# SNES_DRONE_MCU.net
KiCad netlist of a schematic drawn in Altium Designer
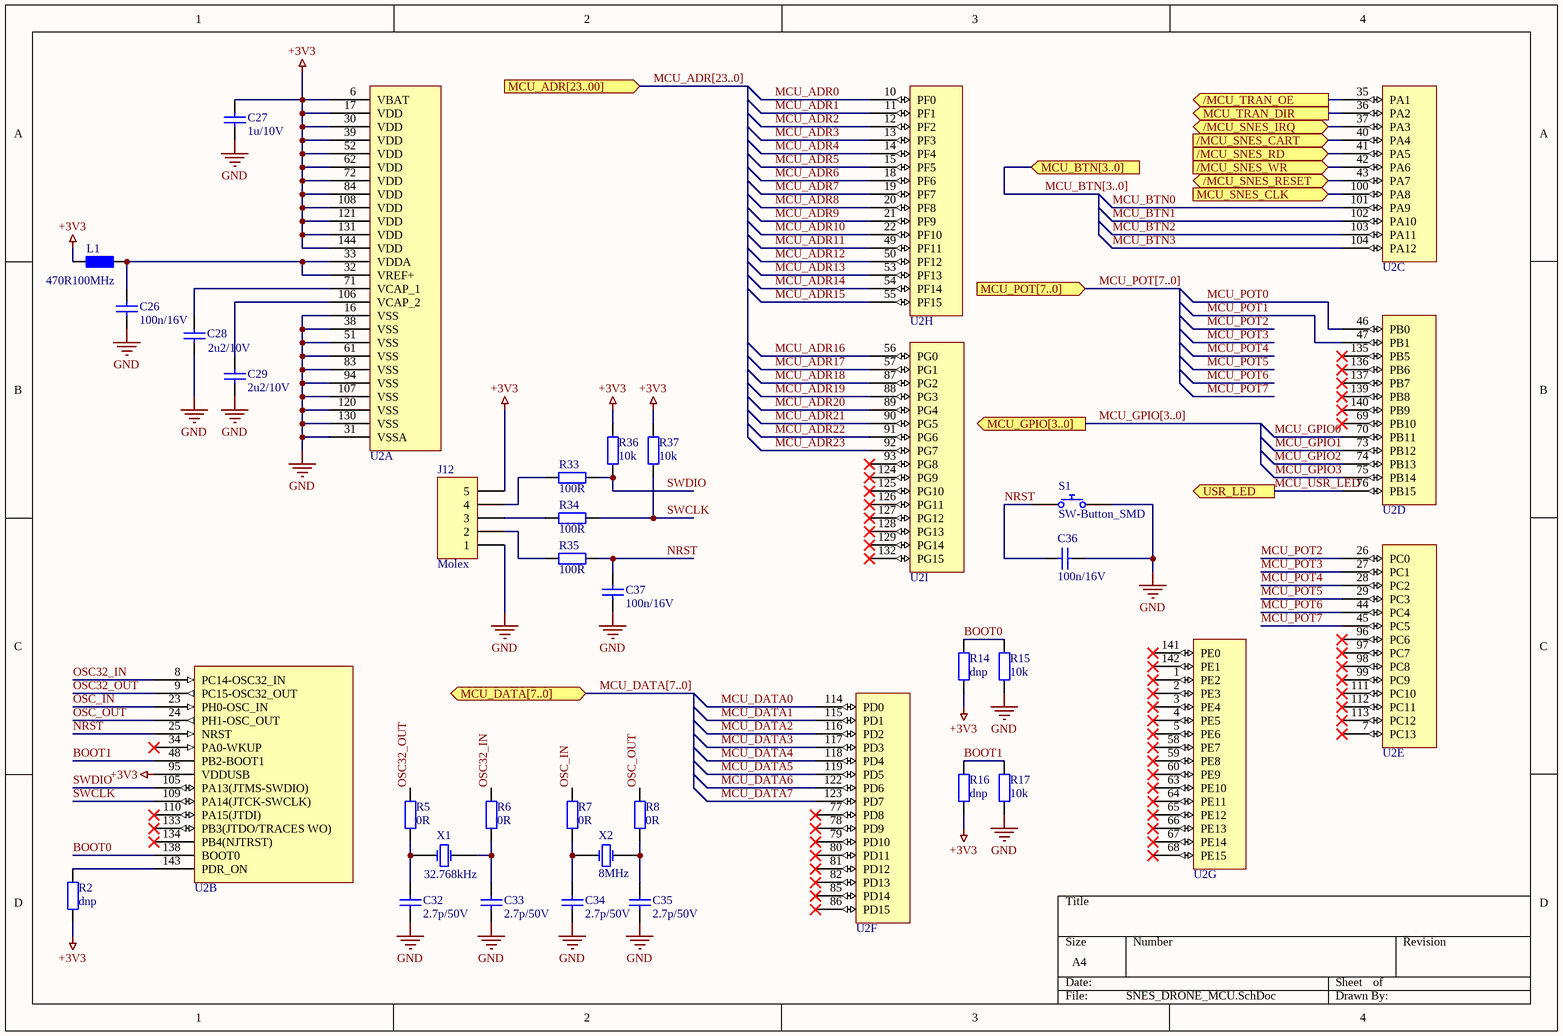
[diagram p0: SNES_DRONE_MCU.SchDoc]

(export (version "E")
  (design (tool "Eeschema 10.0.6"))
  (components
    (comp (ref "C26")
      (value "100n/16V")
      (footprint "0402_RES")
      (description "Keramikvielschichtkondensator, SMD, 0.1 µF, 16 V, 0402 [Metrisch 1005], ± 10%, X5R, Baureihe MC")
      (libsource (lib "My_Integrated_Library") (part "Cap_100n_0402"))
    )
    (comp (ref "C27")
      (value "1u/10V")
      (footprint "0603_RES")
      (description "Keramikvielschichtkondensator, SMD, 1 µF, 10 V, 0603 [Metrisch 1608], ± 20%, X5R, WCAP-CSGP Series")
      (libsource (lib "My_Integrated_Library") (part "Cap_1u_0603"))
    )
    (comp (ref "C28")
      (value "2u2/10V")
      (footprint "0603_RES")
      (libsource (lib "My_Integrated_Library") (part "Cap_2u2_0603"))
    )
    (comp (ref "C29")
      (value "2u2/10V")
      (footprint "0603_RES")
      (libsource (lib "My_Integrated_Library") (part "Cap_2u2_0603"))
    )
    (comp (ref "C32")
      (value "2.7p/50V")
      (footprint "0402_RES")
      (description "Keramikvielschichtkondensator, SMD, 2.7 pF, 50 V, 0402 [Metrisch 1005], ± 0.25pF, C0G / NP0")
      (libsource (lib "My_Integrated_Library") (part "Cap_2p7_0402"))
    )
    (comp (ref "C33")
      (value "2.7p/50V")
      (footprint "0402_RES")
      (description "Keramikvielschichtkondensator, SMD, 2.7 pF, 50 V, 0402 [Metrisch 1005], ± 0.25pF, C0G / NP0")
      (libsource (lib "My_Integrated_Library") (part "Cap_2p7_0402"))
    )
    (comp (ref "C34")
      (value "2.7p/50V")
      (footprint "0402_RES")
      (description "Keramikvielschichtkondensator, SMD, 2.7 pF, 50 V, 0402 [Metrisch 1005], ± 0.25pF, C0G / NP0")
      (libsource (lib "My_Integrated_Library") (part "Cap_2p7_0402"))
    )
    (comp (ref "C35")
      (value "2.7p/50V")
      (footprint "0402_RES")
      (description "Keramikvielschichtkondensator, SMD, 2.7 pF, 50 V, 0402 [Metrisch 1005], ± 0.25pF, C0G / NP0")
      (libsource (lib "My_Integrated_Library") (part "Cap_2p7_0402"))
    )
    (comp (ref "C36")
      (value "100n/16V")
      (footprint "0402_RES")
      (description "Keramikvielschichtkondensator, SMD, 0.1 µF, 16 V, 0402 [Metrisch 1005], ± 10%, X5R, Baureihe MC")
      (libsource (lib "My_Integrated_Library") (part "Cap_100n_0402"))
    )
    (comp (ref "C37")
      (value "100n/16V")
      (footprint "0402_RES")
      (description "Keramikvielschichtkondensator, SMD, 0.1 µF, 16 V, 0402 [Metrisch 1005], ± 10%, X5R, Baureihe MC")
      (libsource (lib "My_Integrated_Library") (part "Cap_100n_0402"))
    )
    (comp (ref "J12")
      (value "MOLEX_22-27-2051")
      (footprint "MOLEX_22-27-2051")
      (description "5 pin molex connector")
      (fields (field (name "MANUFACTURER 1") "Molex"))
      (libsource (lib "My_Integrated_Library") (part "MOLEX_22-27-2051"))
    )
    (comp (ref "L1")
      (value "470R100MHz")
      (footprint "0603_RES")
      (description "BLM18PG471SN1D -  Ferritperle, 0603 [Metrisch 1608], 470 ohm, 1 A, Baureihe BLM18P, 0.2 ohm, ± 25%")
      (libsource (lib "My_Integrated_Library") (part "FER_0603_470R"))
    )
    (comp (ref "R2")
      (value "dnp")
      (footprint "0603_DNP")
      (fields (field (name "Comment") "DNP"))
      (libsource (lib "My_Integrated_Library") (part "RES_DNP"))
    )
    (comp (ref "R5")
      (value "0R")
      (footprint "0603_RES")
      (description "YAGEO 0R")
      (libsource (lib "My_Integrated_Library") (part "RES_0603_0R"))
    )
    (comp (ref "R6")
      (value "0R")
      (footprint "0603_RES")
      (description "YAGEO 0R")
      (libsource (lib "My_Integrated_Library") (part "RES_0603_0R"))
    )
    (comp (ref "R7")
      (value "0R")
      (footprint "0603_RES")
      (description "YAGEO 0R")
      (libsource (lib "My_Integrated_Library") (part "RES_0603_0R"))
    )
    (comp (ref "R8")
      (value "0R")
      (footprint "0603_RES")
      (description "YAGEO 0R")
      (libsource (lib "My_Integrated_Library") (part "RES_0603_0R"))
    )
    (comp (ref "R14")
      (value "dnp")
      (footprint "0603_DNP")
      (fields (field (name "Comment") "DNP"))
      (libsource (lib "My_Integrated_Library") (part "RES_DNP"))
    )
    (comp (ref "R15")
      (value "10k")
      (footprint "0603_RES")
      (description "YAGEO 10kOhm 100mW ± 1%")
      (fields (field (name "Comment") "10kOhm 100mW"))
      (libsource (lib "My_Integrated_Library") (part "RES_0603_10k_100mW"))
    )
    (comp (ref "R16")
      (value "dnp")
      (footprint "0603_DNP")
      (fields (field (name "Comment") "DNP"))
      (libsource (lib "My_Integrated_Library") (part "RES_DNP"))
    )
    (comp (ref "R17")
      (value "10k")
      (footprint "0603_RES")
      (description "YAGEO 10kOhm 100mW ± 1%")
      (fields (field (name "Comment") "10kOhm 100mW"))
      (libsource (lib "My_Integrated_Library") (part "RES_0603_10k_100mW"))
    )
    (comp (ref "R33")
      (value "100R")
      (footprint "0603_RES")
      (description "PANASONIC ELECTRONIC COMPONENTS 100Ohm 100mW ± 1%")
      (fields (field (name "Comment") "100Ohm 100mW"))
      (libsource (lib "My_Integrated_Library") (part "RES_0603_100_100mW"))
    )
    (comp (ref "R34")
      (value "100R")
      (footprint "0603_RES")
      (description "PANASONIC ELECTRONIC COMPONENTS 100Ohm 100mW ± 1%")
      (fields (field (name "Comment") "100Ohm 100mW"))
      (libsource (lib "My_Integrated_Library") (part "RES_0603_100_100mW"))
    )
    (comp (ref "R35")
      (value "100R")
      (footprint "0603_RES")
      (description "PANASONIC ELECTRONIC COMPONENTS 100Ohm 100mW ± 1%")
      (fields (field (name "Comment") "100Ohm 100mW"))
      (libsource (lib "My_Integrated_Library") (part "RES_0603_100_100mW"))
    )
    (comp (ref "R36")
      (value "10k")
      (footprint "0603_RES")
      (description "YAGEO 10kOhm 100mW ± 1%")
      (fields (field (name "Comment") "10kOhm 100mW"))
      (libsource (lib "My_Integrated_Library") (part "RES_0603_10k_100mW"))
    )
    (comp (ref "R37")
      (value "10k")
      (footprint "0603_RES")
      (description "YAGEO 10kOhm 100mW ± 1%")
      (fields (field (name "Comment") "10kOhm 100mW"))
      (libsource (lib "My_Integrated_Library") (part "RES_0603_10k_100mW"))
    )
    (comp (ref "S1")
      (value "SW-Button_SMD")
      (footprint "SKQGAFE010")
      (description "ALPS SMD Push Button")
      (libsource (lib "My_Integrated_Library") (part "SW-Button_SMD"))
    )
    (comp (ref "U2")
      (value "STM32F446ZE")
      (footprint "LQFP144_SMALL_PADS")
      (description "ARM Cortex-M4, 180MHz, 512KB, 128KB")
      (libsource (lib "My_Schlib") (part "STM32F446ZE"))
    )
    (comp (ref "X1")
      (value "32.768kHz")
      (footprint "XTAL_32768khz")
      (libsource (lib "My_Integrated_Library") (part "XTAL_32.768kHz"))
    )
    (comp (ref "X2")
      (value "8MHz")
      (footprint "XTAL_8MHZ")
      (libsource (lib "My_Integrated_Library") (part "XTAL_8MHz"))
    )
  )
  (nets
    (net (code "1") (name "+3V3") (class "Default")
      (node (ref "C27") (pin "2") (pinfunction "2_2") (pintype "passive"))
      (node (ref "J12") (pin "5") (pinfunction "5_5") (pintype "passive"))
      (node (ref "L1") (pin "1") (pinfunction "1_1") (pintype "passive"))
      (node (ref "R14") (pin "1") (pinfunction "1_1") (pintype "passive"))
      (node (ref "R16") (pin "1") (pinfunction "1_1") (pintype "passive"))
      (node (ref "R2") (pin "1") (pinfunction "1_1") (pintype "passive"))
      (node (ref "R36") (pin "2") (pinfunction "2_2") (pintype "passive"))
      (node (ref "R37") (pin "2") (pinfunction "2_2") (pintype "passive"))
      (node (ref "U2") (pin "108") (pinfunction "VDD_108") (pintype "power_in"))
      (node (ref "U2") (pin "121") (pinfunction "VDD_121") (pintype "power_in"))
      (node (ref "U2") (pin "131") (pinfunction "VDD_131") (pintype "power_in"))
      (node (ref "U2") (pin "144") (pinfunction "VDD_144") (pintype "power_in"))
      (node (ref "U2") (pin "17") (pinfunction "VDD_17") (pintype "power_in"))
      (node (ref "U2") (pin "30") (pinfunction "VDD_30") (pintype "power_in"))
      (node (ref "U2") (pin "39") (pinfunction "VDD_39") (pintype "power_in"))
      (node (ref "U2") (pin "52") (pinfunction "VDD_52") (pintype "power_in"))
      (node (ref "U2") (pin "6") (pinfunction "VBAT_6") (pintype "power_in"))
      (node (ref "U2") (pin "62") (pinfunction "VDD_62") (pintype "power_in"))
      (node (ref "U2") (pin "72") (pinfunction "VDD_72") (pintype "power_in"))
      (node (ref "U2") (pin "84") (pinfunction "VDD_84") (pintype "power_in"))
      (node (ref "U2") (pin "95") (pinfunction "VDDUSB_95") (pintype "power_in"))
    )
    (net (code "2") (name "/BOOT0") (class "Default")
      (node (ref "R14") (pin "2") (pinfunction "2_2") (pintype "passive"))
      (node (ref "R15") (pin "2") (pinfunction "2_2") (pintype "passive"))
      (node (ref "U2") (pin "138") (pinfunction "BOOT0_138") (pintype "passive"))
    )
    (net (code "3") (name "/BOOT1") (class "Default")
      (node (ref "R16") (pin "2") (pinfunction "2_2") (pintype "passive"))
      (node (ref "R17") (pin "2") (pinfunction "2_2") (pintype "passive"))
      (node (ref "U2") (pin "48") (pinfunction "PB2-BOOT1_48") (pintype "passive"))
    )
    (net (code "4") (name "/MCU_ADR0") (class "Default")
      (node (ref "U2") (pin "10") (pinfunction "PF0_10") (pintype "bidirectional"))
    )
    (net (code "5") (name "/MCU_ADR1") (class "Default")
      (node (ref "U2") (pin "11") (pinfunction "PF1_11") (pintype "bidirectional"))
    )
    (net (code "6") (name "/MCU_ADR2") (class "Default")
      (node (ref "U2") (pin "12") (pinfunction "PF2_12") (pintype "bidirectional"))
    )
    (net (code "7") (name "/MCU_ADR3") (class "Default")
      (node (ref "U2") (pin "13") (pinfunction "PF3_13") (pintype "bidirectional"))
    )
    (net (code "8") (name "/MCU_ADR4") (class "Default")
      (node (ref "U2") (pin "14") (pinfunction "PF4_14") (pintype "bidirectional"))
    )
    (net (code "9") (name "/MCU_ADR5") (class "Default")
      (node (ref "U2") (pin "15") (pinfunction "PF5_15") (pintype "bidirectional"))
    )
    (net (code "10") (name "/MCU_ADR6") (class "Default")
      (node (ref "U2") (pin "18") (pinfunction "PF6_18") (pintype "bidirectional"))
    )
    (net (code "11") (name "/MCU_ADR7") (class "Default")
      (node (ref "U2") (pin "19") (pinfunction "PF7_19") (pintype "bidirectional"))
    )
    (net (code "12") (name "/MCU_ADR8") (class "Default")
      (node (ref "U2") (pin "20") (pinfunction "PF8_20") (pintype "bidirectional"))
    )
    (net (code "13") (name "/MCU_ADR9") (class "Default")
      (node (ref "U2") (pin "21") (pinfunction "PF9_21") (pintype "bidirectional"))
    )
    (net (code "14") (name "/MCU_ADR10") (class "Default")
      (node (ref "U2") (pin "22") (pinfunction "PF10_22") (pintype "bidirectional"))
    )
    (net (code "15") (name "/MCU_ADR11") (class "Default")
      (node (ref "U2") (pin "49") (pinfunction "PF11_49") (pintype "bidirectional"))
    )
    (net (code "16") (name "/MCU_ADR12") (class "Default")
      (node (ref "U2") (pin "50") (pinfunction "PF12_50") (pintype "bidirectional"))
    )
    (net (code "17") (name "/MCU_ADR13") (class "Default")
      (node (ref "U2") (pin "53") (pinfunction "PF13_53") (pintype "bidirectional"))
    )
    (net (code "18") (name "/MCU_ADR14") (class "Default")
      (node (ref "U2") (pin "54") (pinfunction "PF14_54") (pintype "bidirectional"))
    )
    (net (code "19") (name "/MCU_ADR15") (class "Default")
      (node (ref "U2") (pin "55") (pinfunction "PF15_55") (pintype "bidirectional"))
    )
    (net (code "20") (name "/MCU_ADR16") (class "Default")
      (node (ref "U2") (pin "56") (pinfunction "PG0_56") (pintype "bidirectional"))
    )
    (net (code "21") (name "/MCU_ADR17") (class "Default")
      (node (ref "U2") (pin "57") (pinfunction "PG1_57") (pintype "bidirectional"))
    )
    (net (code "22") (name "/MCU_ADR18") (class "Default")
      (node (ref "U2") (pin "87") (pinfunction "PG2_87") (pintype "bidirectional"))
    )
    (net (code "23") (name "/MCU_ADR19") (class "Default")
      (node (ref "U2") (pin "88") (pinfunction "PG3_88") (pintype "bidirectional"))
    )
    (net (code "24") (name "/MCU_ADR20") (class "Default")
      (node (ref "U2") (pin "89") (pinfunction "PG4_89") (pintype "bidirectional"))
    )
    (net (code "25") (name "/MCU_ADR21") (class "Default")
      (node (ref "U2") (pin "90") (pinfunction "PG5_90") (pintype "bidirectional"))
    )
    (net (code "26") (name "/MCU_ADR22") (class "Default")
      (node (ref "U2") (pin "91") (pinfunction "PG6_91") (pintype "bidirectional"))
    )
    (net (code "27") (name "/MCU_ADR23") (class "Default")
      (node (ref "U2") (pin "92") (pinfunction "PG7_92") (pintype "bidirectional"))
    )
    (net (code "29") (name "/MCU_BTN0") (class "Default")
      (node (ref "U2") (pin "101") (pinfunction "PA9_101") (pintype "bidirectional"))
    )
    (net (code "30") (name "/MCU_BTN1") (class "Default")
      (node (ref "U2") (pin "102") (pinfunction "PA10_102") (pintype "bidirectional"))
    )
    (net (code "31") (name "/MCU_BTN2") (class "Default")
      (node (ref "U2") (pin "103") (pinfunction "PA11_103") (pintype "bidirectional"))
    )
    (net (code "32") (name "/MCU_BTN3") (class "Default")
      (node (ref "U2") (pin "104") (pinfunction "PA12_104") (pintype "bidirectional"))
    )
    (net (code "34") (name "/MCU_DATA0") (class "Default")
      (node (ref "U2") (pin "114") (pinfunction "PD0_114") (pintype "bidirectional"))
    )
    (net (code "35") (name "/MCU_DATA1") (class "Default")
      (node (ref "U2") (pin "115") (pinfunction "PD1_115") (pintype "bidirectional"))
    )
    (net (code "36") (name "/MCU_DATA2") (class "Default")
      (node (ref "U2") (pin "116") (pinfunction "PD2_116") (pintype "bidirectional"))
    )
    (net (code "37") (name "/MCU_DATA3") (class "Default")
      (node (ref "U2") (pin "117") (pinfunction "PD3_117") (pintype "bidirectional"))
    )
    (net (code "38") (name "/MCU_DATA4") (class "Default")
      (node (ref "U2") (pin "118") (pinfunction "PD4_118") (pintype "bidirectional"))
    )
    (net (code "39") (name "/MCU_DATA5") (class "Default")
      (node (ref "U2") (pin "119") (pinfunction "PD5_119") (pintype "bidirectional"))
    )
    (net (code "40") (name "/MCU_DATA6") (class "Default")
      (node (ref "U2") (pin "122") (pinfunction "PD6_122") (pintype "bidirectional"))
    )
    (net (code "41") (name "/MCU_DATA7") (class "Default")
      (node (ref "U2") (pin "123") (pinfunction "PD7_123") (pintype "bidirectional"))
    )
    (net (code "43") (name "/MCU_GPIO0") (class "Default")
      (node (ref "U2") (pin "70") (pinfunction "PB11_70") (pintype "bidirectional"))
    )
    (net (code "44") (name "/MCU_GPIO1") (class "Default")
      (node (ref "U2") (pin "73") (pinfunction "PB12_73") (pintype "bidirectional"))
    )
    (net (code "45") (name "/MCU_GPIO2") (class "Default")
      (node (ref "U2") (pin "74") (pinfunction "PB13_74") (pintype "bidirectional"))
    )
    (net (code "46") (name "/MCU_GPIO3") (class "Default")
      (node (ref "U2") (pin "75") (pinfunction "PB14_75") (pintype "bidirectional"))
    )
    (net (code "48") (name "/MCU_POT0") (class "Default")
      (node (ref "U2") (pin "46") (pinfunction "PB0_46") (pintype "bidirectional"))
    )
    (net (code "49") (name "/MCU_POT1") (class "Default")
      (node (ref "U2") (pin "47") (pinfunction "PB1_47") (pintype "bidirectional"))
    )
    (net (code "50") (name "/MCU_POT2") (class "Default")
      (node (ref "U2") (pin "26") (pinfunction "PC0_26") (pintype "bidirectional"))
    )
    (net (code "51") (name "/MCU_POT3") (class "Default")
      (node (ref "U2") (pin "27") (pinfunction "PC1_27") (pintype "bidirectional"))
    )
    (net (code "52") (name "/MCU_POT4") (class "Default")
      (node (ref "U2") (pin "28") (pinfunction "PC2_28") (pintype "bidirectional"))
    )
    (net (code "53") (name "/MCU_POT5") (class "Default")
      (node (ref "U2") (pin "29") (pinfunction "PC3_29") (pintype "bidirectional"))
    )
    (net (code "54") (name "/MCU_POT6") (class "Default")
      (node (ref "U2") (pin "44") (pinfunction "PC4_44") (pintype "bidirectional"))
    )
    (net (code "55") (name "/MCU_POT7") (class "Default")
      (node (ref "U2") (pin "45") (pinfunction "PC5_45") (pintype "bidirectional"))
    )
    (net (code "57") (name "/MCU_SNES_CLK") (class "Default")
      (node (ref "U2") (pin "100") (pinfunction "PA8_100") (pintype "bidirectional"))
    )
    (net (code "58") (name "/MCU_TRAN_DIR") (class "Default")
      (node (ref "U2") (pin "36") (pinfunction "PA2_36") (pintype "bidirectional"))
    )
    (net (code "59") (name "/MCU_USR_LED") (class "Default")
      (node (ref "U2") (pin "76") (pinfunction "PB15_76") (pintype "bidirectional"))
    )
    (net (code "60") (name "/NRST") (class "Default")
      (node (ref "C36") (pin "1") (pinfunction "1_1") (pintype "passive"))
      (node (ref "C37") (pin "2") (pinfunction "2_2") (pintype "passive"))
      (node (ref "R35") (pin "2") (pinfunction "2_2") (pintype "passive"))
      (node (ref "S1") (pin "1") (pinfunction "1_1") (pintype "passive"))
      (node (ref "U2") (pin "25") (pinfunction "NRST_25") (pintype "input"))
    )
    (net (code "61") (name "/OSC32_IN") (class "Default")
      (node (ref "R6") (pin "2") (pinfunction "2_2") (pintype "passive"))
      (node (ref "U2") (pin "8") (pinfunction "PC14-OSC32_IN_8") (pintype "input"))
    )
    (net (code "62") (name "/OSC32_OUT") (class "Default")
      (node (ref "R5") (pin "2") (pinfunction "2_2") (pintype "passive"))
      (node (ref "U2") (pin "9") (pinfunction "PC15-OSC32_OUT_9") (pintype "output"))
    )
    (net (code "63") (name "/OSC_IN") (class "Default")
      (node (ref "R7") (pin "2") (pinfunction "2_2") (pintype "passive"))
      (node (ref "U2") (pin "23") (pinfunction "PH0-OSC_IN_23") (pintype "input"))
    )
    (net (code "64") (name "/OSC_OUT") (class "Default")
      (node (ref "R8") (pin "2") (pinfunction "2_2") (pintype "passive"))
      (node (ref "U2") (pin "24") (pinfunction "PH1-OSC_OUT_24") (pintype "output"))
    )
    (net (code "65") (name "/SWCLK") (class "Default")
      (node (ref "R34") (pin "2") (pinfunction "2_2") (pintype "passive"))
      (node (ref "R37") (pin "1") (pinfunction "1_1") (pintype "passive"))
      (node (ref "U2") (pin "109") (pinfunction "PA14(JTCK-SWCLK)_109") (pintype "bidirectional"))
    )
    (net (code "66") (name "/SWDIO") (class "Default")
      (node (ref "R33") (pin "2") (pinfunction "2_2") (pintype "passive"))
      (node (ref "R36") (pin "1") (pinfunction "1_1") (pintype "passive"))
      (node (ref "U2") (pin "105") (pinfunction "PA13(JTMS-SWDIO)_105") (pintype "bidirectional"))
    )
    (net (code "67") (name "/{slash}MCU_SNES_CART") (class "Default")
      (node (ref "U2") (pin "40") (pinfunction "PA4_40") (pintype "bidirectional"))
    )
    (net (code "68") (name "/{slash}MCU_SNES_IRQ") (class "Default")
      (node (ref "U2") (pin "37") (pinfunction "PA3_37") (pintype "bidirectional"))
    )
    (net (code "69") (name "/{slash}MCU_SNES_RD") (class "Default")
      (node (ref "U2") (pin "41") (pinfunction "PA5_41") (pintype "bidirectional"))
    )
    (net (code "70") (name "/{slash}MCU_SNES_RESET") (class "Default")
      (node (ref "U2") (pin "43") (pinfunction "PA7_43") (pintype "bidirectional"))
    )
    (net (code "71") (name "/{slash}MCU_SNES_WR") (class "Default")
      (node (ref "U2") (pin "42") (pinfunction "PA6_42") (pintype "bidirectional"))
    )
    (net (code "72") (name "/{slash}MCU_TRAN_OE") (class "Default")
      (node (ref "U2") (pin "35") (pinfunction "PA1_35") (pintype "bidirectional"))
    )
    (net (code "73") (name "GND") (class "Default")
      (node (ref "C26") (pin "1") (pinfunction "1_1") (pintype "passive"))
      (node (ref "C27") (pin "1") (pinfunction "1_1") (pintype "passive"))
      (node (ref "C28") (pin "1") (pinfunction "1_1") (pintype "passive"))
      (node (ref "C29") (pin "1") (pinfunction "1_1") (pintype "passive"))
      (node (ref "C32") (pin "1") (pinfunction "1_1") (pintype "passive"))
      (node (ref "C33") (pin "1") (pinfunction "1_1") (pintype "passive"))
      (node (ref "C34") (pin "1") (pinfunction "1_1") (pintype "passive"))
      (node (ref "C35") (pin "1") (pinfunction "1_1") (pintype "passive"))
      (node (ref "C36") (pin "2") (pinfunction "2_2") (pintype "passive"))
      (node (ref "C37") (pin "1") (pinfunction "1_1") (pintype "passive"))
      (node (ref "J12") (pin "1") (pinfunction "1_1") (pintype "passive"))
      (node (ref "R15") (pin "1") (pinfunction "1_1") (pintype "passive"))
      (node (ref "R17") (pin "1") (pinfunction "1_1") (pintype "passive"))
      (node (ref "S1") (pin "3") (pinfunction "3_3") (pintype "passive"))
      (node (ref "U2") (pin "107") (pinfunction "VSS_107") (pintype "power_in"))
      (node (ref "U2") (pin "120") (pinfunction "VSS_120") (pintype "power_in"))
      (node (ref "U2") (pin "130") (pinfunction "VSS_130") (pintype "power_in"))
      (node (ref "U2") (pin "16") (pinfunction "VSS_16") (pintype "power_in"))
      (node (ref "U2") (pin "31") (pinfunction "VSSA_31") (pintype "power_in"))
      (node (ref "U2") (pin "38") (pinfunction "VSS_38") (pintype "power_in"))
      (node (ref "U2") (pin "51") (pinfunction "VSS_51") (pintype "power_in"))
      (node (ref "U2") (pin "61") (pinfunction "VSS_61") (pintype "power_in"))
      (node (ref "U2") (pin "83") (pinfunction "VSS_83") (pintype "power_in"))
      (node (ref "U2") (pin "94") (pinfunction "VSS_94") (pintype "power_in"))
    )
    (net (code "74") (name "Net-(C32-Pad2)") (class "Default")
      (node (ref "C32") (pin "2") (pinfunction "2_2") (pintype "passive"))
      (node (ref "R5") (pin "1") (pinfunction "1_1") (pintype "passive"))
      (node (ref "X1") (pin "1") (pinfunction "1_1") (pintype "passive"))
    )
    (net (code "75") (name "Net-(C33-Pad2)") (class "Default")
      (node (ref "C33") (pin "2") (pinfunction "2_2") (pintype "passive"))
      (node (ref "R6") (pin "1") (pinfunction "1_1") (pintype "passive"))
      (node (ref "X1") (pin "2") (pinfunction "2_2") (pintype "passive"))
    )
    (net (code "76") (name "Net-(C34-Pad2)") (class "Default")
      (node (ref "C34") (pin "2") (pinfunction "2_2") (pintype "passive"))
      (node (ref "R7") (pin "1") (pinfunction "1_1") (pintype "passive"))
      (node (ref "X2") (pin "1") (pinfunction "1_1") (pintype "passive"))
    )
    (net (code "77") (name "Net-(C35-Pad2)") (class "Default")
      (node (ref "C35") (pin "2") (pinfunction "2_2") (pintype "passive"))
      (node (ref "R8") (pin "1") (pinfunction "1_1") (pintype "passive"))
      (node (ref "X2") (pin "2") (pinfunction "2_2") (pintype "passive"))
    )
    (net (code "78") (name "Net-(J12-Pad2)") (class "Default")
      (node (ref "J12") (pin "2") (pinfunction "2_2") (pintype "passive"))
      (node (ref "R35") (pin "1") (pinfunction "1_1") (pintype "passive"))
    )
    (net (code "79") (name "Net-(J12-Pad3)") (class "Default")
      (node (ref "J12") (pin "3") (pinfunction "3_3") (pintype "passive"))
      (node (ref "R34") (pin "1") (pinfunction "1_1") (pintype "passive"))
    )
    (net (code "80") (name "Net-(J12-Pad4)") (class "Default")
      (node (ref "J12") (pin "4") (pinfunction "4_4") (pintype "passive"))
      (node (ref "R33") (pin "1") (pinfunction "1_1") (pintype "passive"))
    )
    (net (code "81") (name "Net-(U2A-VCAP_1)") (class "Default")
      (node (ref "C28") (pin "2") (pinfunction "2_2") (pintype "passive"))
      (node (ref "U2") (pin "71") (pinfunction "VCAP_1_71") (pintype "passive"))
    )
    (net (code "82") (name "Net-(U2A-VCAP_2)") (class "Default")
      (node (ref "C29") (pin "2") (pinfunction "2_2") (pintype "passive"))
      (node (ref "U2") (pin "106") (pinfunction "VCAP_2_106") (pintype "passive"))
    )
    (net (code "83") (name "Net-(U2A-VDDA)") (class "Default")
      (node (ref "C26") (pin "2") (pinfunction "2_2") (pintype "passive"))
      (node (ref "L1") (pin "2") (pinfunction "2_2") (pintype "passive"))
      (node (ref "U2") (pin "32") (pinfunction "VREF+_32") (pintype "power_in"))
      (node (ref "U2") (pin "33") (pinfunction "VDDA_33") (pintype "power_in"))
    )
    (net (code "84") (name "Net-(U2B-PDR_ON)") (class "Default")
      (node (ref "R2") (pin "2") (pinfunction "2_2") (pintype "passive"))
      (node (ref "U2") (pin "143") (pinfunction "PDR_ON_143") (pintype "passive"))
    )
    (net (code "85") (name "unconnected-(U2B-PA0-WKUP-Pad34)") (class "Default")
      (node (ref "U2") (pin "34") (pinfunction "PA0-WKUP_34") (pintype "input+no_connect"))
    )
    (net (code "86") (name "unconnected-(U2B-PA15(JTDI)-Pad110)") (class "Default")
      (node (ref "U2") (pin "110") (pinfunction "PA15(JTDI)_110") (pintype "bidirectional+no_connect"))
    )
    (net (code "87") (name "unconnected-(U2B-PB3(JTDO{slash}TRACES_WO)-Pad133)") (class "Default")
      (node (ref "U2") (pin "133") (pinfunction "PB3(JTDO/TRACES_WO)_133") (pintype "bidirectional+no_connect"))
    )
    (net (code "88") (name "unconnected-(U2B-PB4(NJTRST)-Pad134)") (class "Default")
      (node (ref "U2") (pin "134") (pinfunction "PB4(NJTRST)_134") (pintype "passive+no_connect"))
    )
    (net (code "89") (name "unconnected-(U2D-PB5-Pad135)") (class "Default")
      (node (ref "U2") (pin "135") (pinfunction "PB5_135") (pintype "bidirectional+no_connect"))
    )
    (net (code "90") (name "unconnected-(U2D-PB6-Pad136)") (class "Default")
      (node (ref "U2") (pin "136") (pinfunction "PB6_136") (pintype "bidirectional+no_connect"))
    )
    (net (code "91") (name "unconnected-(U2D-PB7-Pad137)") (class "Default")
      (node (ref "U2") (pin "137") (pinfunction "PB7_137") (pintype "bidirectional+no_connect"))
    )
    (net (code "92") (name "unconnected-(U2D-PB8-Pad139)") (class "Default")
      (node (ref "U2") (pin "139") (pinfunction "PB8_139") (pintype "bidirectional+no_connect"))
    )
    (net (code "93") (name "unconnected-(U2D-PB9-Pad140)") (class "Default")
      (node (ref "U2") (pin "140") (pinfunction "PB9_140") (pintype "bidirectional+no_connect"))
    )
    (net (code "94") (name "unconnected-(U2D-PB10-Pad69)") (class "Default")
      (node (ref "U2") (pin "69") (pinfunction "PB10_69") (pintype "bidirectional+no_connect"))
    )
    (net (code "95") (name "unconnected-(U2E-PC6-Pad96)") (class "Default")
      (node (ref "U2") (pin "96") (pinfunction "PC6_96") (pintype "bidirectional+no_connect"))
    )
    (net (code "96") (name "unconnected-(U2E-PC7-Pad97)") (class "Default")
      (node (ref "U2") (pin "97") (pinfunction "PC7_97") (pintype "bidirectional+no_connect"))
    )
    (net (code "97") (name "unconnected-(U2E-PC8-Pad98)") (class "Default")
      (node (ref "U2") (pin "98") (pinfunction "PC8_98") (pintype "bidirectional+no_connect"))
    )
    (net (code "98") (name "unconnected-(U2E-PC9-Pad99)") (class "Default")
      (node (ref "U2") (pin "99") (pinfunction "PC9_99") (pintype "bidirectional+no_connect"))
    )
    (net (code "99") (name "unconnected-(U2E-PC10-Pad111)") (class "Default")
      (node (ref "U2") (pin "111") (pinfunction "PC10_111") (pintype "bidirectional+no_connect"))
    )
    (net (code "100") (name "unconnected-(U2E-PC11-Pad112)") (class "Default")
      (node (ref "U2") (pin "112") (pinfunction "PC11_112") (pintype "bidirectional+no_connect"))
    )
    (net (code "101") (name "unconnected-(U2E-PC12-Pad113)") (class "Default")
      (node (ref "U2") (pin "113") (pinfunction "PC12_113") (pintype "bidirectional+no_connect"))
    )
    (net (code "102") (name "unconnected-(U2E-PC13-Pad7)") (class "Default")
      (node (ref "U2") (pin "7") (pinfunction "PC13_7") (pintype "bidirectional+no_connect"))
    )
    (net (code "103") (name "unconnected-(U2F-PD8-Pad77)") (class "Default")
      (node (ref "U2") (pin "77") (pinfunction "PD8_77") (pintype "bidirectional+no_connect"))
    )
    (net (code "104") (name "unconnected-(U2F-PD9-Pad78)") (class "Default")
      (node (ref "U2") (pin "78") (pinfunction "PD9_78") (pintype "bidirectional+no_connect"))
    )
    (net (code "105") (name "unconnected-(U2F-PD10-Pad79)") (class "Default")
      (node (ref "U2") (pin "79") (pinfunction "PD10_79") (pintype "bidirectional+no_connect"))
    )
    (net (code "106") (name "unconnected-(U2F-PD11-Pad80)") (class "Default")
      (node (ref "U2") (pin "80") (pinfunction "PD11_80") (pintype "bidirectional+no_connect"))
    )
    (net (code "107") (name "unconnected-(U2F-PD12-Pad81)") (class "Default")
      (node (ref "U2") (pin "81") (pinfunction "PD12_81") (pintype "bidirectional+no_connect"))
    )
    (net (code "108") (name "unconnected-(U2F-PD13-Pad82)") (class "Default")
      (node (ref "U2") (pin "82") (pinfunction "PD13_82") (pintype "bidirectional+no_connect"))
    )
    (net (code "109") (name "unconnected-(U2F-PD14-Pad85)") (class "Default")
      (node (ref "U2") (pin "85") (pinfunction "PD14_85") (pintype "bidirectional+no_connect"))
    )
    (net (code "110") (name "unconnected-(U2F-PD15-Pad86)") (class "Default")
      (node (ref "U2") (pin "86") (pinfunction "PD15_86") (pintype "bidirectional+no_connect"))
    )
    (net (code "111") (name "unconnected-(U2G-PE0-Pad141)") (class "Default")
      (node (ref "U2") (pin "141") (pinfunction "PE0_141") (pintype "bidirectional+no_connect"))
    )
    (net (code "112") (name "unconnected-(U2G-PE1-Pad142)") (class "Default")
      (node (ref "U2") (pin "142") (pinfunction "PE1_142") (pintype "bidirectional+no_connect"))
    )
    (net (code "113") (name "unconnected-(U2G-PE2-Pad1)") (class "Default")
      (node (ref "U2") (pin "1") (pinfunction "PE2_1") (pintype "bidirectional+no_connect"))
    )
    (net (code "114") (name "unconnected-(U2G-PE3-Pad2)") (class "Default")
      (node (ref "U2") (pin "2") (pinfunction "PE3_2") (pintype "bidirectional+no_connect"))
    )
    (net (code "115") (name "unconnected-(U2G-PE4-Pad3)") (class "Default")
      (node (ref "U2") (pin "3") (pinfunction "PE4_3") (pintype "bidirectional+no_connect"))
    )
    (net (code "116") (name "unconnected-(U2G-PE5-Pad4)") (class "Default")
      (node (ref "U2") (pin "4") (pinfunction "PE5_4") (pintype "bidirectional+no_connect"))
    )
    (net (code "117") (name "unconnected-(U2G-PE6-Pad5)") (class "Default")
      (node (ref "U2") (pin "5") (pinfunction "PE6_5") (pintype "bidirectional+no_connect"))
    )
    (net (code "118") (name "unconnected-(U2G-PE7-Pad58)") (class "Default")
      (node (ref "U2") (pin "58") (pinfunction "PE7_58") (pintype "bidirectional+no_connect"))
    )
    (net (code "119") (name "unconnected-(U2G-PE8-Pad59)") (class "Default")
      (node (ref "U2") (pin "59") (pinfunction "PE8_59") (pintype "bidirectional+no_connect"))
    )
    (net (code "120") (name "unconnected-(U2G-PE9-Pad60)") (class "Default")
      (node (ref "U2") (pin "60") (pinfunction "PE9_60") (pintype "bidirectional+no_connect"))
    )
    (net (code "121") (name "unconnected-(U2G-PE10-Pad63)") (class "Default")
      (node (ref "U2") (pin "63") (pinfunction "PE10_63") (pintype "bidirectional+no_connect"))
    )
    (net (code "122") (name "unconnected-(U2G-PE11-Pad64)") (class "Default")
      (node (ref "U2") (pin "64") (pinfunction "PE11_64") (pintype "bidirectional+no_connect"))
    )
    (net (code "123") (name "unconnected-(U2G-PE12-Pad65)") (class "Default")
      (node (ref "U2") (pin "65") (pinfunction "PE12_65") (pintype "bidirectional+no_connect"))
    )
    (net (code "124") (name "unconnected-(U2G-PE13-Pad66)") (class "Default")
      (node (ref "U2") (pin "66") (pinfunction "PE13_66") (pintype "bidirectional+no_connect"))
    )
    (net (code "125") (name "unconnected-(U2G-PE14-Pad67)") (class "Default")
      (node (ref "U2") (pin "67") (pinfunction "PE14_67") (pintype "bidirectional+no_connect"))
    )
    (net (code "126") (name "unconnected-(U2G-PE15-Pad68)") (class "Default")
      (node (ref "U2") (pin "68") (pinfunction "PE15_68") (pintype "bidirectional+no_connect"))
    )
    (net (code "127") (name "unconnected-(U2I-PG8-Pad93)") (class "Default")
      (node (ref "U2") (pin "93") (pinfunction "PG8_93") (pintype "bidirectional+no_connect"))
    )
    (net (code "128") (name "unconnected-(U2I-PG9-Pad124)") (class "Default")
      (node (ref "U2") (pin "124") (pinfunction "PG9_124") (pintype "bidirectional+no_connect"))
    )
    (net (code "129") (name "unconnected-(U2I-PG10-Pad125)") (class "Default")
      (node (ref "U2") (pin "125") (pinfunction "PG10_125") (pintype "bidirectional+no_connect"))
    )
    (net (code "130") (name "unconnected-(U2I-PG11-Pad126)") (class "Default")
      (node (ref "U2") (pin "126") (pinfunction "PG11_126") (pintype "bidirectional+no_connect"))
    )
    (net (code "131") (name "unconnected-(U2I-PG12-Pad127)") (class "Default")
      (node (ref "U2") (pin "127") (pinfunction "PG12_127") (pintype "bidirectional+no_connect"))
    )
    (net (code "132") (name "unconnected-(U2I-PG13-Pad128)") (class "Default")
      (node (ref "U2") (pin "128") (pinfunction "PG13_128") (pintype "bidirectional+no_connect"))
    )
    (net (code "133") (name "unconnected-(U2I-PG14-Pad129)") (class "Default")
      (node (ref "U2") (pin "129") (pinfunction "PG14_129") (pintype "bidirectional+no_connect"))
    )
    (net (code "134") (name "unconnected-(U2I-PG15-Pad132)") (class "Default")
      (node (ref "U2") (pin "132") (pinfunction "PG15_132") (pintype "bidirectional+no_connect"))
    )
  )
)
